# Connectors.net
KiCad netlist of a schematic drawn in Altium Designer
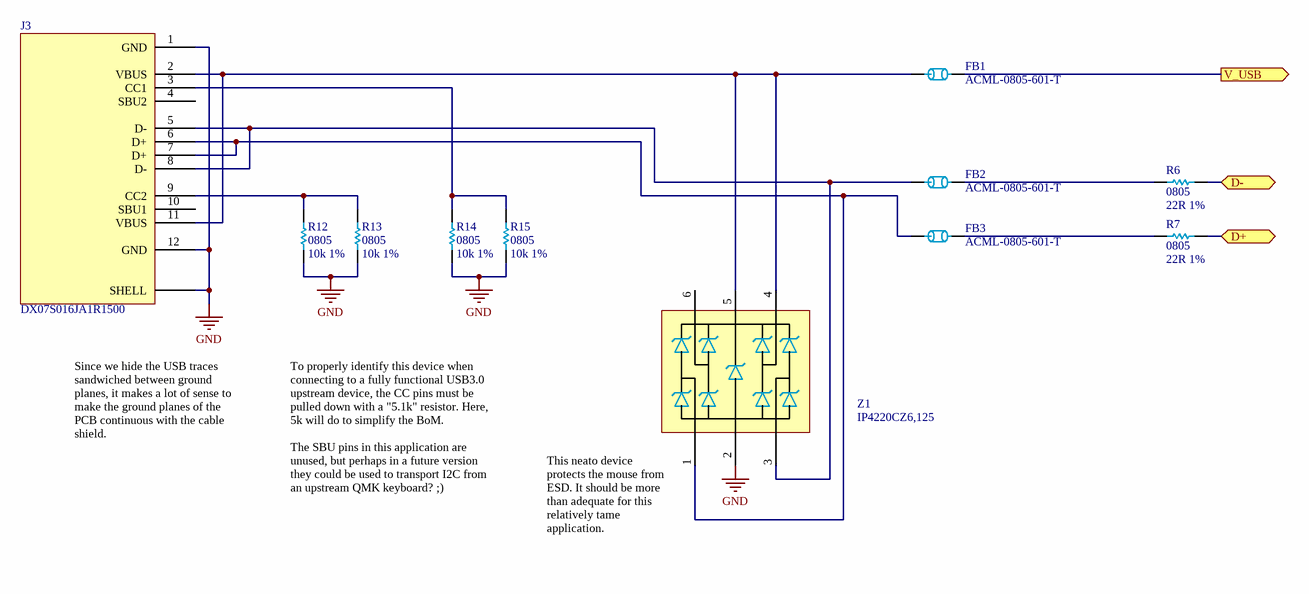
[diagram p0: Connectors.SchDoc]

(export (version "E")
  (design (tool "Eeschema 10.0.6"))
  (components
    (comp (ref "FB1")
      (value "ACML-0805-601-T")
      (footprint "0805")
      (description "FERRITE BEAD 600 OHM 0805 1LN")
      (libsource (lib "Chip_Passives") (part "ACML-0805-601-T"))
    )
    (comp (ref "FB2")
      (value "ACML-0805-601-T")
      (footprint "0805")
      (description "FERRITE BEAD 600 OHM 0805 1LN")
      (libsource (lib "Chip_Passives") (part "ACML-0805-601-T"))
    )
    (comp (ref "FB3")
      (value "ACML-0805-601-T")
      (footprint "0805")
      (description "FERRITE BEAD 600 OHM 0805 1LN")
      (libsource (lib "Chip_Passives") (part "ACML-0805-601-T"))
    )
    (comp (ref "J3")
      (value "DX07S016JA1R1500")
      (footprint "DX07S016JA1R1500")
      (libsource (lib "Connectors") (part "DX07S016JA1R1500"))
    )
    (comp (ref "R6")
      (value "0805")
      (footprint "0805")
      (description "Chip resistor")
      (fields (field (name "ALTIUM_VALUE") "22R 1%"))
      (libsource (lib "Chip_Passives") (part "Res 22R 1% 0805"))
    )
    (comp (ref "R7")
      (value "0805")
      (footprint "0805")
      (description "Chip resistor")
      (fields (field (name "ALTIUM_VALUE") "22R 1%"))
      (libsource (lib "Chip_Passives") (part "Res 22R 1% 0805"))
    )
    (comp (ref "R12")
      (value "0805")
      (footprint "0805")
      (description "Chip resistor")
      (fields (field (name "ALTIUM_VALUE") "10k 1%"))
      (libsource (lib "Chip_Passives") (part "Res 10k 1% 0805"))
    )
    (comp (ref "R13")
      (value "0805")
      (footprint "0805")
      (description "Chip resistor")
      (fields (field (name "ALTIUM_VALUE") "10k 1%"))
      (libsource (lib "Chip_Passives") (part "Res 10k 1% 0805"))
    )
    (comp (ref "R14")
      (value "0805")
      (footprint "0805")
      (description "Chip resistor")
      (fields (field (name "ALTIUM_VALUE") "10k 1%"))
      (libsource (lib "Chip_Passives") (part "Res 10k 1% 0805"))
    )
    (comp (ref "R15")
      (value "0805")
      (footprint "0805")
      (description "Chip resistor")
      (fields (field (name "ALTIUM_VALUE") "10k 1%"))
      (libsource (lib "Chip_Passives") (part "Res 10k 1% 0805"))
    )
    (comp (ref "Z1")
      (value "IP4220CZ6,125")
      (footprint "PESD3V3S4UD - SOT95P275X110-6N")
      (description "TVS DIODE 5.5V 6TSOP (Low capacitance, USB)")
      (libsource (lib "Diodes") (part "IP4220CZ6,125"))
    )
  )
  (nets
    (net (code "1") (name "/D+") (class "Default")
      (node (ref "R7") (pin "2") (pinfunction "2_2") (pintype "passive"))
    )
    (net (code "2") (name "/D-") (class "Default")
      (node (ref "R6") (pin "2") (pinfunction "2_2") (pintype "passive"))
    )
    (net (code "3") (name "/V_USB") (class "Default")
      (node (ref "FB1") (pin "2") (pinfunction "2_2") (pintype "passive"))
    )
    (net (code "4") (name "GND") (class "Default")
      (node (ref "J3") (pin "1") (pinfunction "GND_1") (pintype "passive"))
      (node (ref "J3") (pin "12") (pinfunction "GND_12") (pintype "passive"))
      (node (ref "J3") (pin "SHELL") (pinfunction "SHELL_SHELL") (pintype "passive"))
      (node (ref "R12") (pin "1") (pinfunction "1_1") (pintype "passive"))
      (node (ref "R13") (pin "1") (pinfunction "1_1") (pintype "passive"))
      (node (ref "R14") (pin "1") (pinfunction "1_1") (pintype "passive"))
      (node (ref "R15") (pin "1") (pinfunction "1_1") (pintype "passive"))
      (node (ref "Z1") (pin "2") (pinfunction "2_2") (pintype "passive"))
    )
    (net (code "5") (name "Net-(FB1-Pad1)") (class "Default")
      (node (ref "FB1") (pin "1") (pinfunction "1_1") (pintype "passive"))
      (node (ref "J3") (pin "11") (pinfunction "VBUS_11") (pintype "passive"))
      (node (ref "J3") (pin "2") (pinfunction "VBUS_2") (pintype "passive"))
      (node (ref "Z1") (pin "4") (pinfunction "4_4") (pintype "passive"))
      (node (ref "Z1") (pin "5") (pinfunction "5_5") (pintype "passive"))
    )
    (net (code "6") (name "Net-(FB2-Pad1)") (class "Default")
      (node (ref "FB2") (pin "1") (pinfunction "1_1") (pintype "passive"))
      (node (ref "J3") (pin "5") (pinfunction "D-_5") (pintype "passive"))
      (node (ref "J3") (pin "8") (pinfunction "D-_8") (pintype "passive"))
      (node (ref "Z1") (pin "3") (pinfunction "3_3") (pintype "passive"))
    )
    (net (code "7") (name "Net-(FB2-Pad2)") (class "Default")
      (node (ref "FB2") (pin "2") (pinfunction "2_2") (pintype "passive"))
      (node (ref "R6") (pin "1") (pinfunction "1_1") (pintype "passive"))
    )
    (net (code "8") (name "Net-(FB3-Pad1)") (class "Default")
      (node (ref "FB3") (pin "1") (pinfunction "1_1") (pintype "passive"))
      (node (ref "J3") (pin "6") (pinfunction "D+_6") (pintype "passive"))
      (node (ref "J3") (pin "7") (pinfunction "D+_7") (pintype "passive"))
      (node (ref "Z1") (pin "1") (pinfunction "1_1") (pintype "passive"))
    )
    (net (code "9") (name "Net-(FB3-Pad2)") (class "Default")
      (node (ref "FB3") (pin "2") (pinfunction "2_2") (pintype "passive"))
      (node (ref "R7") (pin "1") (pinfunction "1_1") (pintype "passive"))
    )
    (net (code "10") (name "Net-(J3-CC1)") (class "Default")
      (node (ref "J3") (pin "3") (pinfunction "CC1_3") (pintype "passive"))
      (node (ref "R14") (pin "2") (pinfunction "2_2") (pintype "passive"))
      (node (ref "R15") (pin "2") (pinfunction "2_2") (pintype "passive"))
    )
    (net (code "11") (name "Net-(J3-CC2)") (class "Default")
      (node (ref "J3") (pin "9") (pinfunction "CC2_9") (pintype "passive"))
      (node (ref "R12") (pin "2") (pinfunction "2_2") (pintype "passive"))
      (node (ref "R13") (pin "2") (pinfunction "2_2") (pintype "passive"))
    )
    (net (code "12") (name "unconnected-(J3-SBU1-Pad10)") (class "Default")
      (node (ref "J3") (pin "10") (pinfunction "SBU1_10") (pintype "passive"))
    )
    (net (code "13") (name "unconnected-(J3-SBU2-Pad4)") (class "Default")
      (node (ref "J3") (pin "4") (pinfunction "SBU2_4") (pintype "passive"))
    )
    (net (code "14") (name "unconnected-(Z1-Pad6)") (class "Default")
      (node (ref "Z1") (pin "6") (pinfunction "6_6") (pintype "passive"))
    )
  )
)
